# Sheet1.net
KiCad netlist of a schematic drawn in Altium Designer
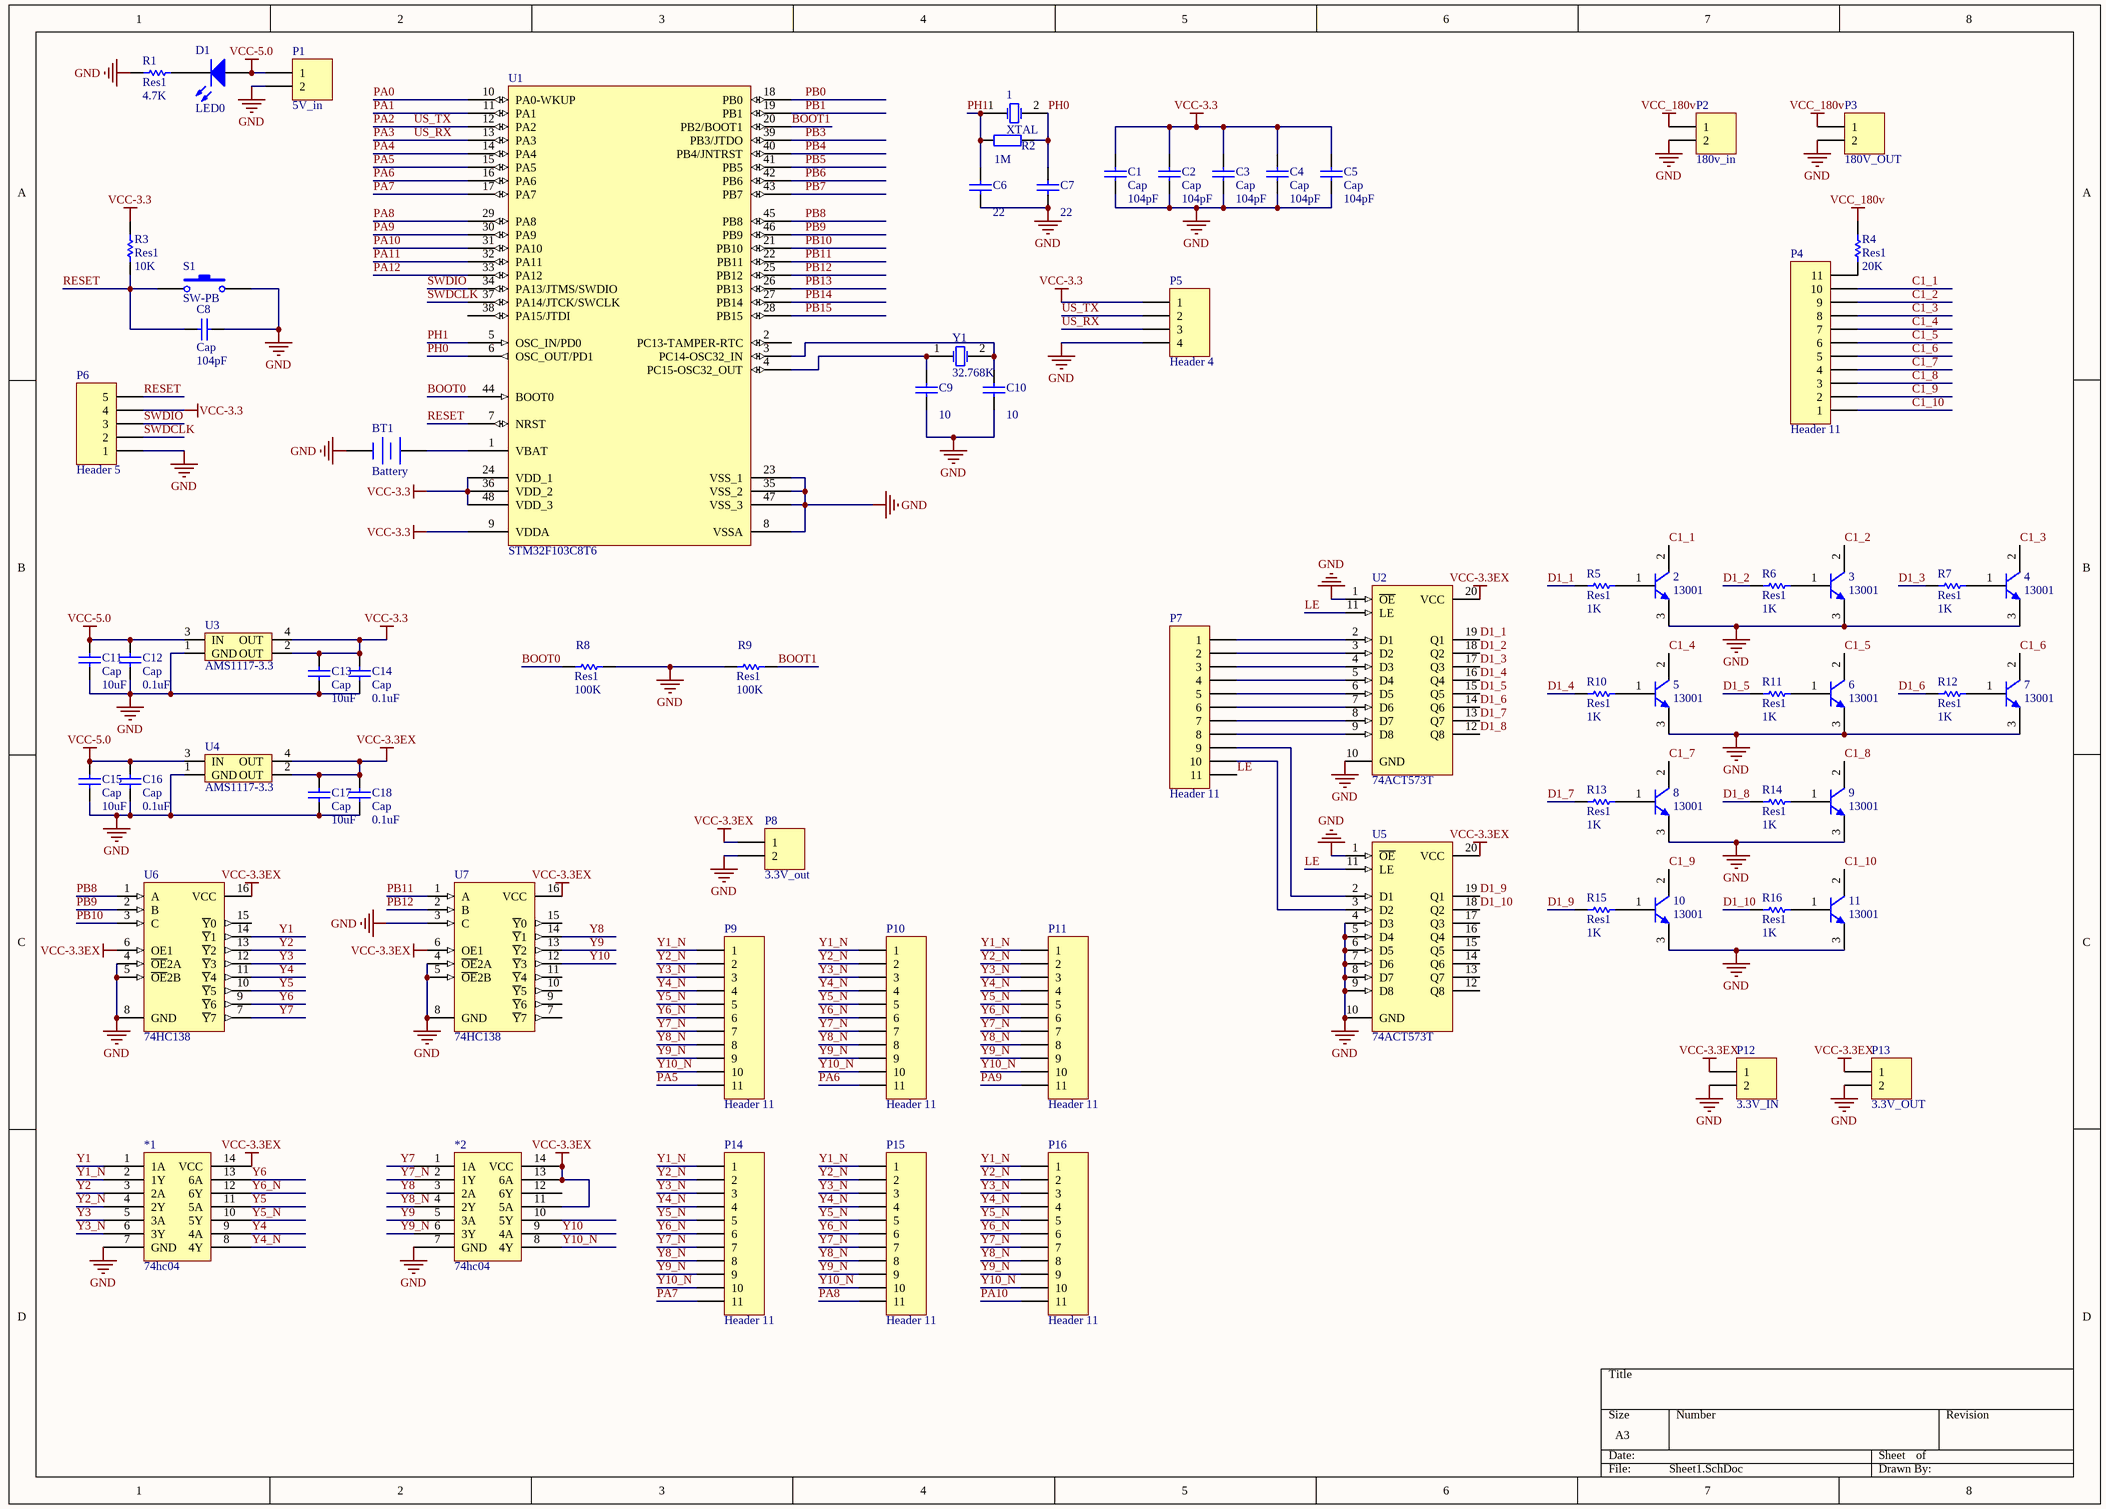
[diagram p0: Sheet1.SchDoc]

(export (version "E")
  (design (tool "Eeschema 10.0.6"))
  (components
    (comp (ref "*1")
      (value "74hc04")
      (footprint "DIP-14")
      (description "非门")
      (libsource (lib "辉光管原理图库") (part "74hc04"))
    )
    (comp (ref "*2")
      (value "74hc04")
      (footprint "DIP-14")
      (description "非门")
      (libsource (lib "辉光管原理图库") (part "74hc04"))
    )
    (comp (ref "1")
      (value "XTAL")
      (footprint "49S-SMD")
      (description "Crystal Oscillator")
      (fields (field (name "PUBLISHER") "Altium Limited"))
      (libsource (lib "Miscellaneous Devices") (part "XTAL"))
    )
    (comp (ref "2")
      (value "13001")
      (footprint "TO-92A")
      (description "NPN三极管")
      (fields (field (name "PUBLISHER") "Altium Limited"))
      (libsource (lib "fszhang(2)") (part "13001"))
    )
    (comp (ref "3")
      (value "13001")
      (footprint "TO-92A")
      (description "NPN三极管")
      (fields (field (name "PUBLISHER") "Altium Limited"))
      (libsource (lib "fszhang(2)") (part "13001"))
    )
    (comp (ref "4")
      (value "13001")
      (footprint "TO-92A")
      (description "NPN三极管")
      (fields (field (name "PUBLISHER") "Altium Limited"))
      (libsource (lib "fszhang(2)") (part "13001"))
    )
    (comp (ref "5")
      (value "13001")
      (footprint "TO-92A")
      (description "NPN三极管")
      (fields (field (name "PUBLISHER") "Altium Limited"))
      (libsource (lib "fszhang(2)") (part "13001"))
    )
    (comp (ref "6")
      (value "13001")
      (footprint "TO-92A")
      (description "NPN三极管")
      (fields (field (name "PUBLISHER") "Altium Limited"))
      (libsource (lib "fszhang(2)") (part "13001"))
    )
    (comp (ref "7")
      (value "13001")
      (footprint "TO-92A")
      (description "NPN三极管")
      (fields (field (name "PUBLISHER") "Altium Limited"))
      (libsource (lib "fszhang(2)") (part "13001"))
    )
    (comp (ref "8")
      (value "13001")
      (footprint "TO-92A")
      (description "NPN三极管")
      (fields (field (name "PUBLISHER") "Altium Limited"))
      (libsource (lib "fszhang(2)") (part "13001"))
    )
    (comp (ref "9")
      (value "13001")
      (footprint "TO-92A")
      (description "NPN三极管")
      (fields (field (name "PUBLISHER") "Altium Limited"))
      (libsource (lib "fszhang(2)") (part "13001"))
    )
    (comp (ref "10")
      (value "13001")
      (footprint "TO-92A")
      (description "NPN三极管")
      (fields (field (name "PUBLISHER") "Altium Limited"))
      (libsource (lib "fszhang(2)") (part "13001"))
    )
    (comp (ref "11")
      (value "13001")
      (footprint "TO-92A")
      (description "NPN三极管")
      (fields (field (name "PUBLISHER") "Altium Limited"))
      (libsource (lib "fszhang(2)") (part "13001"))
    )
    (comp (ref "BT1")
      (value "Battery")
      (footprint "CR1220")
      (description "备份电池")
      (fields (field (name "PUBLISHER") "Altium Limited"))
      (libsource (lib "fszhang(2)") (part "Battery"))
    )
    (comp (ref "C1")
      (value "Cap")
      (footprint "0603-1")
      (description "Capacitor")
      (fields (field (name "ALTIUM_VALUE") "104pF") (field (name "PUBLISHER") "Altium Limited"))
      (libsource (lib "Miscellaneous Devices") (part "Cap"))
    )
    (comp (ref "C2")
      (value "Cap")
      (footprint "0603-1")
      (description "Capacitor")
      (fields (field (name "ALTIUM_VALUE") "104pF") (field (name "PUBLISHER") "Altium Limited"))
      (libsource (lib "Miscellaneous Devices") (part "Cap"))
    )
    (comp (ref "C3")
      (value "Cap")
      (footprint "0603-1")
      (description "Capacitor")
      (fields (field (name "ALTIUM_VALUE") "104pF") (field (name "PUBLISHER") "Altium Limited"))
      (libsource (lib "Miscellaneous Devices") (part "Cap"))
    )
    (comp (ref "C4")
      (value "Cap")
      (footprint "0603-1")
      (description "Capacitor")
      (fields (field (name "ALTIUM_VALUE") "104pF") (field (name "PUBLISHER") "Altium Limited"))
      (libsource (lib "Miscellaneous Devices") (part "Cap"))
    )
    (comp (ref "C5")
      (value "Cap")
      (footprint "0603-1")
      (description "Capacitor")
      (fields (field (name "ALTIUM_VALUE") "104pF") (field (name "PUBLISHER") "Altium Limited"))
      (libsource (lib "Miscellaneous Devices") (part "Cap"))
    )
    (comp (ref "C6")
      (value "22")
      (footprint "0603-1")
      (description "Capacitor")
      (fields (field (name "PUBLISHER") "Altium Limited"))
      (libsource (lib "Miscellaneous Devices") (part "Cap"))
    )
    (comp (ref "C7")
      (value "22")
      (footprint "0603-1")
      (description "Capacitor")
      (fields (field (name "PUBLISHER") "Altium Limited"))
      (libsource (lib "Miscellaneous Devices") (part "Cap"))
    )
    (comp (ref "C8")
      (value "Cap")
      (footprint "0603-1")
      (description "Capacitor")
      (fields (field (name "ALTIUM_VALUE") "104pF") (field (name "PUBLISHER") "Altium Limited"))
      (libsource (lib "Miscellaneous Devices") (part "Cap"))
    )
    (comp (ref "C9")
      (value "10")
      (footprint "0603-1")
      (description "Capacitor")
      (fields (field (name "PUBLISHER") "Altium Limited"))
      (libsource (lib "Miscellaneous Devices") (part "Cap"))
    )
    (comp (ref "C10")
      (value "10")
      (footprint "0603-1")
      (description "Capacitor")
      (fields (field (name "PUBLISHER") "Altium Limited"))
      (libsource (lib "Miscellaneous Devices") (part "Cap"))
    )
    (comp (ref "C11")
      (value "Cap")
      (footprint "0603-1")
      (description "Capacitor")
      (fields (field (name "ALTIUM_VALUE") "10uF") (field (name "PUBLISHER") "Altium Limited"))
      (libsource (lib "Miscellaneous Devices") (part "Cap"))
    )
    (comp (ref "C12")
      (value "Cap")
      (footprint "0603-1")
      (description "Capacitor")
      (fields (field (name "ALTIUM_VALUE") "0.1uF") (field (name "PUBLISHER") "Altium Limited"))
      (libsource (lib "Miscellaneous Devices") (part "Cap"))
    )
    (comp (ref "C13")
      (value "Cap")
      (footprint "0603-1")
      (description "Capacitor")
      (fields (field (name "ALTIUM_VALUE") "10uF") (field (name "PUBLISHER") "Altium Limited"))
      (libsource (lib "Miscellaneous Devices") (part "Cap"))
    )
    (comp (ref "C14")
      (value "Cap")
      (footprint "0603-1")
      (description "Capacitor")
      (fields (field (name "ALTIUM_VALUE") "0.1uF") (field (name "PUBLISHER") "Altium Limited"))
      (libsource (lib "Miscellaneous Devices") (part "Cap"))
    )
    (comp (ref "C15")
      (value "Cap")
      (footprint "0603-1")
      (description "Capacitor")
      (fields (field (name "ALTIUM_VALUE") "10uF") (field (name "PUBLISHER") "Altium Limited"))
      (libsource (lib "Miscellaneous Devices") (part "Cap"))
    )
    (comp (ref "C16")
      (value "Cap")
      (footprint "0603-1")
      (description "Capacitor")
      (fields (field (name "ALTIUM_VALUE") "0.1uF") (field (name "PUBLISHER") "Altium Limited"))
      (libsource (lib "Miscellaneous Devices") (part "Cap"))
    )
    (comp (ref "C17")
      (value "Cap")
      (footprint "0603-1")
      (description "Capacitor")
      (fields (field (name "ALTIUM_VALUE") "10uF") (field (name "PUBLISHER") "Altium Limited"))
      (libsource (lib "Miscellaneous Devices") (part "Cap"))
    )
    (comp (ref "C18")
      (value "Cap")
      (footprint "0603-1")
      (description "Capacitor")
      (fields (field (name "ALTIUM_VALUE") "0.1uF") (field (name "PUBLISHER") "Altium Limited"))
      (libsource (lib "Miscellaneous Devices") (part "Cap"))
    )
    (comp (ref "D1")
      (value "LED0")
      (footprint "LED0805")
      (description "Typical INFRARED GaAs LED")
      (fields (field (name "PUBLISHER") "Altium Limited"))
      (libsource (lib "Miscellaneous Devices") (part "LED0"))
    )
    (comp (ref "P1")
      (value "5V_in")
      (footprint "XH2.54-2")
      (description "Header, 2-Pin")
      (fields (field (name "PUBLISHER") "Altium Limited"))
      (libsource (lib "Miscellaneous Connectors") (part "Header 2"))
    )
    (comp (ref "P2")
      (value "180v_in")
      (footprint "XH2.54-2")
      (description "Header, 2-Pin")
      (fields (field (name "PUBLISHER") "Altium Limited"))
      (libsource (lib "Miscellaneous Connectors") (part "Header 2"))
    )
    (comp (ref "P3")
      (value "180V_OUT")
      (footprint "XH2.54-2")
      (description "Header, 2-Pin")
      (fields (field (name "PUBLISHER") "Altium Limited"))
      (libsource (lib "Miscellaneous Connectors") (part "Header 2"))
    )
    (comp (ref "P4")
      (value "Header 11")
      (footprint "SMT11P")
      (description "Header, 11-Pin")
      (fields (field (name "PUBLISHER") "Altium Limited"))
      (libsource (lib "") (part "Header 11_2"))
    )
    (comp (ref "P5")
      (value "Header 4")
      (footprint "HDR1X4")
      (description "Header, 4-Pin")
      (fields (field (name "PUBLISHER") "Altium Limited"))
      (libsource (lib "Miscellaneous Connectors") (part "Header 4"))
    )
    (comp (ref "P6")
      (value "Header 5")
      (footprint "HDR1X5")
      (description "Header, 5-Pin")
      (fields (field (name "PUBLISHER") "Altium Limited"))
      (libsource (lib "Miscellaneous Connectors") (part "Header 5"))
    )
    (comp (ref "P7")
      (value "Header 11")
      (footprint "SMT11P")
      (description "Header, 11-Pin")
      (fields (field (name "PUBLISHER") "Altium Limited"))
      (libsource (lib "") (part "Header 11_1"))
    )
    (comp (ref "P8")
      (value "3.3V_out")
      (footprint "XH2.54-2")
      (description "Header, 2-Pin")
      (fields (field (name "PUBLISHER") "Altium Limited"))
      (libsource (lib "Miscellaneous Connectors") (part "Header 2"))
    )
    (comp (ref "P9")
      (value "Header 11")
      (footprint "SMT11P")
      (description "Header, 11-Pin")
      (fields (field (name "PUBLISHER") "Altium Limited"))
      (libsource (lib "Miscellaneous Connectors") (part "Header 11"))
    )
    (comp (ref "P10")
      (value "Header 11")
      (footprint "SMT11P")
      (description "Header, 11-Pin")
      (fields (field (name "PUBLISHER") "Altium Limited"))
      (libsource (lib "Miscellaneous Connectors") (part "Header 11"))
    )
    (comp (ref "P11")
      (value "Header 11")
      (footprint "SMT11P")
      (description "Header, 11-Pin")
      (fields (field (name "PUBLISHER") "Altium Limited"))
      (libsource (lib "Miscellaneous Connectors") (part "Header 11"))
    )
    (comp (ref "P12")
      (value "3.3V_IN")
      (footprint "XH2.54-2")
      (description "Header, 2-Pin")
      (fields (field (name "PUBLISHER") "Altium Limited"))
      (libsource (lib "Miscellaneous Connectors") (part "Header 2"))
    )
    (comp (ref "P13")
      (value "3.3V_OUT")
      (footprint "XH2.54-2")
      (description "Header, 2-Pin")
      (fields (field (name "PUBLISHER") "Altium Limited"))
      (libsource (lib "Miscellaneous Connectors") (part "Header 2"))
    )
    (comp (ref "P14")
      (value "Header 11")
      (footprint "SMT11P")
      (description "Header, 11-Pin")
      (fields (field (name "PUBLISHER") "Altium Limited"))
      (libsource (lib "Miscellaneous Connectors") (part "Header 11"))
    )
    (comp (ref "P15")
      (value "Header 11")
      (footprint "SMT11P")
      (description "Header, 11-Pin")
      (fields (field (name "PUBLISHER") "Altium Limited"))
      (libsource (lib "Miscellaneous Connectors") (part "Header 11"))
    )
    (comp (ref "P16")
      (value "Header 11")
      (footprint "SMT11P")
      (description "Header, 11-Pin")
      (fields (field (name "PUBLISHER") "Altium Limited"))
      (libsource (lib "Miscellaneous Connectors") (part "Header 11"))
    )
    (comp (ref "R1")
      (value "Res1")
      (footprint "0603-1")
      (description "Resistor")
      (fields (field (name "ALTIUM_VALUE") "4.7K") (field (name "PUBLISHER") "Altium Limited"))
      (libsource (lib "Miscellaneous Devices") (part "Res1"))
    )
    (comp (ref "R2")
      (value "1M")
      (footprint "0603-1")
      (description "Resistor")
      (fields (field (name "PUBLISHER") "Altium Limited"))
      (libsource (lib "Miscellaneous Devices") (part "Res2"))
    )
    (comp (ref "R3")
      (value "Res1")
      (footprint "0603-1")
      (description "Resistor")
      (fields (field (name "ALTIUM_VALUE") "10K") (field (name "PUBLISHER") "Altium Limited"))
      (libsource (lib "Miscellaneous Devices") (part "Res1"))
    )
    (comp (ref "R4")
      (value "Res1")
      (footprint "0805-1R")
      (description "Resistor")
      (fields (field (name "ALTIUM_VALUE") "20K") (field (name "PUBLISHER") "Altium Limited"))
      (libsource (lib "Miscellaneous Devices") (part "Res1"))
    )
    (comp (ref "R5")
      (value "Res1")
      (footprint "0603R")
      (description "Resistor")
      (fields (field (name "ALTIUM_VALUE") "1K") (field (name "PUBLISHER") "Altium Limited"))
      (libsource (lib "Miscellaneous Devices") (part "Res1"))
    )
    (comp (ref "R6")
      (value "Res1")
      (footprint "0603R")
      (description "Resistor")
      (fields (field (name "ALTIUM_VALUE") "1K") (field (name "PUBLISHER") "Altium Limited"))
      (libsource (lib "Miscellaneous Devices") (part "Res1"))
    )
    (comp (ref "R7")
      (value "Res1")
      (footprint "0603R")
      (description "Resistor")
      (fields (field (name "ALTIUM_VALUE") "1K") (field (name "PUBLISHER") "Altium Limited"))
      (libsource (lib "Miscellaneous Devices") (part "Res1"))
    )
    (comp (ref "R8")
      (value "Res1")
      (footprint "0603-1")
      (description "Resistor")
      (fields (field (name "ALTIUM_VALUE") "100K") (field (name "PUBLISHER") "Altium Limited"))
      (libsource (lib "Miscellaneous Devices") (part "Res1"))
    )
    (comp (ref "R9")
      (value "Res1")
      (footprint "0603-1")
      (description "Resistor")
      (fields (field (name "ALTIUM_VALUE") "100K") (field (name "PUBLISHER") "Altium Limited"))
      (libsource (lib "Miscellaneous Devices") (part "Res1"))
    )
    (comp (ref "R10")
      (value "Res1")
      (footprint "0603R")
      (description "Resistor")
      (fields (field (name "ALTIUM_VALUE") "1K") (field (name "PUBLISHER") "Altium Limited"))
      (libsource (lib "Miscellaneous Devices") (part "Res1"))
    )
    (comp (ref "R11")
      (value "Res1")
      (footprint "0603R")
      (description "Resistor")
      (fields (field (name "ALTIUM_VALUE") "1K") (field (name "PUBLISHER") "Altium Limited"))
      (libsource (lib "Miscellaneous Devices") (part "Res1"))
    )
    (comp (ref "R12")
      (value "Res1")
      (footprint "0603R")
      (description "Resistor")
      (fields (field (name "ALTIUM_VALUE") "1K") (field (name "PUBLISHER") "Altium Limited"))
      (libsource (lib "Miscellaneous Devices") (part "Res1"))
    )
    (comp (ref "R13")
      (value "Res1")
      (footprint "0603R")
      (description "Resistor")
      (fields (field (name "ALTIUM_VALUE") "1K") (field (name "PUBLISHER") "Altium Limited"))
      (libsource (lib "Miscellaneous Devices") (part "Res1"))
    )
    (comp (ref "R14")
      (value "Res1")
      (footprint "0603R")
      (description "Resistor")
      (fields (field (name "ALTIUM_VALUE") "1K") (field (name "PUBLISHER") "Altium Limited"))
      (libsource (lib "Miscellaneous Devices") (part "Res1"))
    )
    (comp (ref "R15")
      (value "Res1")
      (footprint "0603R")
      (description "Resistor")
      (fields (field (name "ALTIUM_VALUE") "1K") (field (name "PUBLISHER") "Altium Limited"))
      (libsource (lib "Miscellaneous Devices") (part "Res1"))
    )
    (comp (ref "R16")
      (value "Res1")
      (footprint "0603R")
      (description "Resistor")
      (fields (field (name "ALTIUM_VALUE") "1K") (field (name "PUBLISHER") "Altium Limited"))
      (libsource (lib "Miscellaneous Devices") (part "Res1"))
    )
    (comp (ref "S1")
      (value "SW-PB")
      (footprint "KEY-SMD1")
      (description "Switch")
      (fields (field (name "PUBLISHER") "Altium Limited"))
      (libsource (lib "Miscellaneous Devices") (part "SW-PB"))
    )
    (comp (ref "U1")
      (value "STM32F103C8T6")
      (footprint "LQFP48_N")
      (description "STM32 ARM-based 32-bit MCU with 64 Kbytes Flash, 48-pin LQFP, Industrial Temperature")
      (fields (field (name "PUBLISHER") "Altium Limited"))
      (libsource (lib "ST Microcontroller 32-Bit STM32") (part "STM32F103C8T6"))
    )
    (comp (ref "U2")
      (value "74ACT573T")
      (footprint "DIP-20")
      (description "双向数据传输")
      (fields (field (name "PUBLISHER") "Altium Limited"))
      (libsource (lib "fszhang(2)") (part "74ACT573T"))
    )
    (comp (ref "U3")
      (value "AMS1117-3.3")
      (footprint "AMS1117")
      (libsource (lib "Explorer STM32F407封装库") (part "AMS1117"))
    )
    (comp (ref "U4")
      (value "AMS1117-3.3")
      (footprint "AMS1117")
      (libsource (lib "Explorer STM32F407封装库") (part "AMS1117"))
    )
    (comp (ref "U5")
      (value "74ACT573T")
      (footprint "DIP-20")
      (description "双向数据传输")
      (fields (field (name "PUBLISHER") "Altium Limited"))
      (libsource (lib "fszhang(2)") (part "74ACT573T"))
    )
    (comp (ref "U6")
      (value "74HC138")
      (footprint "DIP-16")
      (description "138译码器")
      (fields (field (name "PUBLISHER") "Altium Limited"))
      (libsource (lib "fszhang(2)") (part "74HC138"))
    )
    (comp (ref "U7")
      (value "74HC138")
      (footprint "DIP-16")
      (description "138译码器")
      (fields (field (name "PUBLISHER") "Altium Limited"))
      (libsource (lib "fszhang(2)") (part "74HC138"))
    )
    (comp (ref "Y1")
      (value "32.768K")
      (footprint "XTAL32")
      (description "Crystal Oscillator")
      (fields (field (name "PUBLISHER") "Altium Limited"))
      (libsource (lib "Explorer STM32F407封装库") (part "XTAL_1"))
    )
  )
  (nets
    (net (code "1") (name "/BOOT0") (class "Default")
      (node (ref "R8") (pin "1") (pinfunction "1_1") (pintype "passive"))
      (node (ref "U1") (pin "44") (pinfunction "BOOT0_44") (pintype "input"))
    )
    (net (code "2") (name "/BOOT1") (class "Default")
      (node (ref "R9") (pin "2") (pinfunction "2_2") (pintype "passive"))
      (node (ref "U1") (pin "20") (pinfunction "PB2/BOOT1_20") (pintype "bidirectional"))
    )
    (net (code "3") (name "/C1_1") (class "Default")
      (node (ref "2") (pin "2") (pinfunction "C_2") (pintype "passive"))
      (node (ref "P4") (pin "10") (pinfunction "10_10") (pintype "passive"))
    )
    (net (code "4") (name "/C1_2") (class "Default")
      (node (ref "3") (pin "2") (pinfunction "C_2") (pintype "passive"))
      (node (ref "P4") (pin "9") (pinfunction "9_9") (pintype "passive"))
    )
    (net (code "5") (name "/C1_3") (class "Default")
      (node (ref "4") (pin "2") (pinfunction "C_2") (pintype "passive"))
      (node (ref "P4") (pin "8") (pinfunction "8_8") (pintype "passive"))
    )
    (net (code "6") (name "/C1_4") (class "Default")
      (node (ref "5") (pin "2") (pinfunction "C_2") (pintype "passive"))
      (node (ref "P4") (pin "7") (pinfunction "7_7") (pintype "passive"))
    )
    (net (code "7") (name "/C1_5") (class "Default")
      (node (ref "6") (pin "2") (pinfunction "C_2") (pintype "passive"))
      (node (ref "P4") (pin "6") (pinfunction "6_6") (pintype "passive"))
    )
    (net (code "8") (name "/C1_6") (class "Default")
      (node (ref "7") (pin "2") (pinfunction "C_2") (pintype "passive"))
      (node (ref "P4") (pin "5") (pinfunction "5_5") (pintype "passive"))
    )
    (net (code "9") (name "/C1_7") (class "Default")
      (node (ref "8") (pin "2") (pinfunction "C_2") (pintype "passive"))
      (node (ref "P4") (pin "4") (pinfunction "4_4") (pintype "passive"))
    )
    (net (code "10") (name "/C1_8") (class "Default")
      (node (ref "9") (pin "2") (pinfunction "C_2") (pintype "passive"))
      (node (ref "P4") (pin "3") (pinfunction "3_3") (pintype "passive"))
    )
    (net (code "11") (name "/C1_9") (class "Default")
      (node (ref "10") (pin "2") (pinfunction "C_2") (pintype "passive"))
      (node (ref "P4") (pin "2") (pinfunction "2_2") (pintype "passive"))
    )
    (net (code "12") (name "/C1_10") (class "Default")
      (node (ref "11") (pin "2") (pinfunction "C_2") (pintype "passive"))
      (node (ref "P4") (pin "1") (pinfunction "1_1") (pintype "passive"))
    )
    (net (code "13") (name "/D1_1") (class "Default")
      (node (ref "R5") (pin "1") (pinfunction "1_1") (pintype "passive"))
      (node (ref "U2") (pin "19") (pinfunction "Q1_19") (pintype "tri_state"))
    )
    (net (code "14") (name "/D1_2") (class "Default")
      (node (ref "R6") (pin "1") (pinfunction "1_1") (pintype "passive"))
      (node (ref "U2") (pin "18") (pinfunction "Q2_18") (pintype "tri_state"))
    )
    (net (code "15") (name "/D1_3") (class "Default")
      (node (ref "R7") (pin "1") (pinfunction "1_1") (pintype "passive"))
      (node (ref "U2") (pin "17") (pinfunction "Q3_17") (pintype "tri_state"))
    )
    (net (code "16") (name "/D1_4") (class "Default")
      (node (ref "R10") (pin "1") (pinfunction "1_1") (pintype "passive"))
      (node (ref "U2") (pin "16") (pinfunction "Q4_16") (pintype "tri_state"))
    )
    (net (code "17") (name "/D1_5") (class "Default")
      (node (ref "R11") (pin "1") (pinfunction "1_1") (pintype "passive"))
      (node (ref "U2") (pin "15") (pinfunction "Q5_15") (pintype "tri_state"))
    )
    (net (code "18") (name "/D1_6") (class "Default")
      (node (ref "R12") (pin "1") (pinfunction "1_1") (pintype "passive"))
      (node (ref "U2") (pin "14") (pinfunction "Q6_14") (pintype "tri_state"))
    )
    (net (code "19") (name "/D1_7") (class "Default")
      (node (ref "R13") (pin "1") (pinfunction "1_1") (pintype "passive"))
      (node (ref "U2") (pin "13") (pinfunction "Q7_13") (pintype "tri_state"))
    )
    (net (code "20") (name "/D1_8") (class "Default")
      (node (ref "R14") (pin "1") (pinfunction "1_1") (pintype "passive"))
      (node (ref "U2") (pin "12") (pinfunction "Q8_12") (pintype "tri_state"))
    )
    (net (code "21") (name "/D1_9") (class "Default")
      (node (ref "R15") (pin "1") (pinfunction "1_1") (pintype "passive"))
      (node (ref "U5") (pin "19") (pinfunction "Q1_19") (pintype "tri_state"))
    )
    (net (code "22") (name "/D1_10") (class "Default")
      (node (ref "R16") (pin "1") (pinfunction "1_1") (pintype "passive"))
      (node (ref "U5") (pin "18") (pinfunction "Q2_18") (pintype "tri_state"))
    )
    (net (code "23") (name "/LE") (class "Default")
      (node (ref "P7") (pin "11") (pinfunction "11_11") (pintype "passive"))
      (node (ref "U2") (pin "11") (pinfunction "LE_11") (pintype "input"))
      (node (ref "U5") (pin "11") (pinfunction "LE_11") (pintype "input"))
    )
    (net (code "24") (name "/PA0") (class "Default")
      (node (ref "U1") (pin "10") (pinfunction "PA0-WKUP_10") (pintype "bidirectional"))
    )
    (net (code "25") (name "/PA1") (class "Default")
      (node (ref "U1") (pin "11") (pinfunction "PA1_11") (pintype "bidirectional"))
    )
    (net (code "26") (name "/PA2") (class "Default")
      (node (ref "P5") (pin "2") (pinfunction "2_2") (pintype "passive"))
      (node (ref "U1") (pin "12") (pinfunction "PA2_12") (pintype "bidirectional"))
    )
    (net (code "27") (name "/PA3") (class "Default")
      (node (ref "P5") (pin "3") (pinfunction "3_3") (pintype "passive"))
      (node (ref "U1") (pin "13") (pinfunction "PA3_13") (pintype "bidirectional"))
    )
    (net (code "28") (name "/PA4") (class "Default")
      (node (ref "U1") (pin "14") (pinfunction "PA4_14") (pintype "bidirectional"))
    )
    (net (code "29") (name "/PA5") (class "Default")
      (node (ref "P9") (pin "11") (pinfunction "11_11") (pintype "passive"))
      (node (ref "U1") (pin "15") (pinfunction "PA5_15") (pintype "bidirectional"))
    )
    (net (code "30") (name "/PA6") (class "Default")
      (node (ref "P10") (pin "11") (pinfunction "11_11") (pintype "passive"))
      (node (ref "U1") (pin "16") (pinfunction "PA6_16") (pintype "bidirectional"))
    )
    (net (code "31") (name "/PA7") (class "Default")
      (node (ref "P14") (pin "11") (pinfunction "11_11") (pintype "passive"))
      (node (ref "U1") (pin "17") (pinfunction "PA7_17") (pintype "bidirectional"))
    )
    (net (code "32") (name "/PA8") (class "Default")
      (node (ref "P15") (pin "11") (pinfunction "11_11") (pintype "passive"))
      (node (ref "U1") (pin "29") (pinfunction "PA8_29") (pintype "bidirectional"))
    )
    (net (code "33") (name "/PA9") (class "Default")
      (node (ref "P11") (pin "11") (pinfunction "11_11") (pintype "passive"))
      (node (ref "U1") (pin "30") (pinfunction "PA9_30") (pintype "bidirectional"))
    )
    (net (code "34") (name "/PA10") (class "Default")
      (node (ref "P16") (pin "11") (pinfunction "11_11") (pintype "passive"))
      (node (ref "U1") (pin "31") (pinfunction "PA10_31") (pintype "bidirectional"))
    )
    (net (code "35") (name "/PA11") (class "Default")
      (node (ref "U1") (pin "32") (pinfunction "PA11_32") (pintype "bidirectional"))
    )
    (net (code "36") (name "/PA12") (class "Default")
      (node (ref "U1") (pin "33") (pinfunction "PA12_33") (pintype "bidirectional"))
    )
    (net (code "37") (name "/PB0") (class "Default")
      (node (ref "U1") (pin "18") (pinfunction "PB0_18") (pintype "bidirectional"))
    )
    (net (code "38") (name "/PB1") (class "Default")
      (node (ref "U1") (pin "19") (pinfunction "PB1_19") (pintype "bidirectional"))
    )
    (net (code "39") (name "/PB3") (class "Default")
      (node (ref "U1") (pin "39") (pinfunction "PB3/JTDO_39") (pintype "bidirectional"))
    )
    (net (code "40") (name "/PB4") (class "Default")
      (node (ref "U1") (pin "40") (pinfunction "PB4/JNTRST_40") (pintype "bidirectional"))
    )
    (net (code "41") (name "/PB5") (class "Default")
      (node (ref "U1") (pin "41") (pinfunction "PB5_41") (pintype "bidirectional"))
    )
    (net (code "42") (name "/PB6") (class "Default")
      (node (ref "U1") (pin "42") (pinfunction "PB6_42") (pintype "bidirectional"))
    )
    (net (code "43") (name "/PB7") (class "Default")
      (node (ref "U1") (pin "43") (pinfunction "PB7_43") (pintype "bidirectional"))
    )
    (net (code "44") (name "/PB8") (class "Default")
      (node (ref "U1") (pin "45") (pinfunction "PB8_45") (pintype "bidirectional"))
      (node (ref "U6") (pin "1") (pinfunction "A_1") (pintype "input"))
    )
    (net (code "45") (name "/PB9") (class "Default")
      (node (ref "U1") (pin "46") (pinfunction "PB9_46") (pintype "bidirectional"))
      (node (ref "U6") (pin "2") (pinfunction "B_2") (pintype "input"))
    )
    (net (code "46") (name "/PB10") (class "Default")
      (node (ref "U1") (pin "21") (pinfunction "PB10_21") (pintype "bidirectional"))
      (node (ref "U6") (pin "3") (pinfunction "C_3") (pintype "input"))
    )
    (net (code "47") (name "/PB11") (class "Default")
      (node (ref "U1") (pin "22") (pinfunction "PB11_22") (pintype "bidirectional"))
      (node (ref "U7") (pin "1") (pinfunction "A_1") (pintype "input"))
    )
    (net (code "48") (name "/PB12") (class "Default")
      (node (ref "U1") (pin "25") (pinfunction "PB12_25") (pintype "bidirectional"))
      (node (ref "U7") (pin "2") (pinfunction "B_2") (pintype "input"))
    )
    (net (code "49") (name "/PB13") (class "Default")
      (node (ref "U1") (pin "26") (pinfunction "PB13_26") (pintype "bidirectional"))
    )
    (net (code "50") (name "/PB14") (class "Default")
      (node (ref "U1") (pin "27") (pinfunction "PB14_27") (pintype "bidirectional"))
    )
    (net (code "51") (name "/PB15") (class "Default")
      (node (ref "U1") (pin "28") (pinfunction "PB15_28") (pintype "bidirectional"))
    )
    (net (code "52") (name "/PH0") (class "Default")
      (node (ref "1") (pin "2") (pinfunction "OSC2_2") (pintype "passive"))
      (node (ref "C7") (pin "1") (pinfunction "1_1") (pintype "passive"))
      (node (ref "R2") (pin "1") (pinfunction "1_1") (pintype "passive"))
      (node (ref "U1") (pin "6") (pinfunction "OSC_OUT/PD1_6") (pintype "output"))
    )
    (net (code "53") (name "/PH1") (class "Default")
      (node (ref "1") (pin "1") (pinfunction "OSC1_1") (pintype "passive"))
      (node (ref "C6") (pin "2") (pinfunction "2_2") (pintype "passive"))
      (node (ref "R2") (pin "2") (pinfunction "2_2") (pintype "passive"))
      (node (ref "U1") (pin "5") (pinfunction "OSC_IN/PD0_5") (pintype "input"))
    )
    (net (code "54") (name "/RESET") (class "Default")
      (node (ref "C8") (pin "2") (pinfunction "2_2") (pintype "passive"))
      (node (ref "P6") (pin "5") (pinfunction "5_5") (pintype "passive"))
      (node (ref "R3") (pin "1") (pinfunction "1_1") (pintype "passive"))
      (node (ref "S1") (pin "1") (pinfunction "1_1") (pintype "passive"))
      (node (ref "U1") (pin "7") (pinfunction "NRST_7") (pintype "bidirectional"))
    )
    (net (code "55") (name "/SWDCLK") (class "Default")
      (node (ref "P6") (pin "2") (pinfunction "2_2") (pintype "passive"))
      (node (ref "U1") (pin "37") (pinfunction "PA14/JTCK/SWCLK_37") (pintype "bidirectional"))
    )
    (net (code "56") (name "/SWDIO") (class "Default")
      (node (ref "P6") (pin "3") (pinfunction "3_3") (pintype "passive"))
      (node (ref "U1") (pin "34") (pinfunction "PA13/JTMS/SWDIO_34") (pintype "bidirectional"))
    )
    (net (code "57") (name "/Y1") (class "Default")
      (node (ref "*1") (pin "1") (pinfunction "1A_1") (pintype "passive"))
      (node (ref "U6") (pin "14") (pinfunction "~{Y}1_14") (pintype "output"))
    )
    (net (code "58") (name "/Y1_N") (class "Default")
      (node (ref "*1") (pin "2") (pinfunction "1Y_2") (pintype "passive"))
      (node (ref "P10") (pin "1") (pinfunction "1_1") (pintype "passive"))
      (node (ref "P11") (pin "1") (pinfunction "1_1") (pintype "passive"))
      (node (ref "P14") (pin "1") (pinfunction "1_1") (pintype "passive"))
      (node (ref "P15") (pin "1") (pinfunction "1_1") (pintype "passive"))
      (node (ref "P16") (pin "1") (pinfunction "1_1") (pintype "passive"))
      (node (ref "P9") (pin "1") (pinfunction "1_1") (pintype "passive"))
    )
    (net (code "59") (name "/Y2") (class "Default")
      (node (ref "*1") (pin "3") (pinfunction "2A_3") (pintype "passive"))
      (node (ref "U6") (pin "13") (pinfunction "~{Y}2_13") (pintype "output"))
    )
    (net (code "60") (name "/Y2_N") (class "Default")
      (node (ref "*1") (pin "4") (pinfunction "2Y_4") (pintype "passive"))
      (node (ref "P10") (pin "2") (pinfunction "2_2") (pintype "passive"))
      (node (ref "P11") (pin "2") (pinfunction "2_2") (pintype "passive"))
      (node (ref "P14") (pin "2") (pinfunction "2_2") (pintype "passive"))
      (node (ref "P15") (pin "2") (pinfunction "2_2") (pintype "passive"))
      (node (ref "P16") (pin "2") (pinfunction "2_2") (pintype "passive"))
      (node (ref "P9") (pin "2") (pinfunction "2_2") (pintype "passive"))
    )
    (net (code "61") (name "/Y3") (class "Default")
      (node (ref "*1") (pin "5") (pinfunction "3A_5") (pintype "passive"))
      (node (ref "U6") (pin "12") (pinfunction "~{Y}3_12") (pintype "output"))
    )
    (net (code "62") (name "/Y3_N") (class "Default")
      (node (ref "*1") (pin "6") (pinfunction "3Y_6") (pintype "passive"))
      (node (ref "P10") (pin "3") (pinfunction "3_3") (pintype "passive"))
      (node (ref "P11") (pin "3") (pinfunction "3_3") (pintype "passive"))
      (node (ref "P14") (pin "3") (pinfunction "3_3") (pintype "passive"))
      (node (ref "P15") (pin "3") (pinfunction "3_3") (pintype "passive"))
      (node (ref "P16") (pin "3") (pinfunction "3_3") (pintype "passive"))
      (node (ref "P9") (pin "3") (pinfunction "3_3") (pintype "passive"))
    )
    (net (code "63") (name "/Y4") (class "Default")
      (node (ref "*1") (pin "9") (pinfunction "4A_9") (pintype "passive"))
      (node (ref "U6") (pin "11") (pinfunction "~{Y}4_11") (pintype "output"))
    )
    (net (code "64") (name "/Y4_N") (class "Default")
      (node (ref "*1") (pin "8") (pinfunction "4Y_8") (pintype "passive"))
      (node (ref "P10") (pin "4") (pinfunction "4_4") (pintype "passive"))
      (node (ref "P11") (pin "4") (pinfunction "4_4") (pintype "passive"))
      (node (ref "P14") (pin "4") (pinfunction "4_4") (pintype "passive"))
      (node (ref "P15") (pin "4") (pinfunction "4_4") (pintype "passive"))
      (node (ref "P16") (pin "4") (pinfunction "4_4") (pintype "passive"))
      (node (ref "P9") (pin "4") (pinfunction "4_4") (pintype "passive"))
    )
    (net (code "65") (name "/Y5") (class "Default")
      (node (ref "*1") (pin "11") (pinfunction "5A_11") (pintype "passive"))
      (node (ref "U6") (pin "10") (pinfunction "~{Y}5_10") (pintype "output"))
    )
    (net (code "66") (name "/Y5_N") (class "Default")
      (node (ref "*1") (pin "10") (pinfunction "5Y_10") (pintype "passive"))
      (node (ref "P10") (pin "5") (pinfunction "5_5") (pintype "passive"))
      (node (ref "P11") (pin "5") (pinfunction "5_5") (pintype "passive"))
      (node (ref "P14") (pin "5") (pinfunction "5_5") (pintype "passive"))
      (node (ref "P15") (pin "5") (pinfunction "5_5") (pintype "passive"))
      (node (ref "P16") (pin "5") (pinfunction "5_5") (pintype "passive"))
      (node (ref "P9") (pin "5") (pinfunction "5_5") (pintype "passive"))
    )
    (net (code "67") (name "/Y6") (class "Default")
      (node (ref "*1") (pin "13") (pinfunction "6A_13") (pintype "passive"))
      (node (ref "U6") (pin "9") (pinfunction "~{Y}6_9") (pintype "output"))
    )
    (net (code "68") (name "/Y6_N") (class "Default")
      (node (ref "*1") (pin "12") (pinfunction "6Y_12") (pintype "passive"))
      (node (ref "P10") (pin "6") (pinfunction "6_6") (pintype "passive"))
      (node (ref "P11") (pin "6") (pinfunction "6_6") (pintype "passive"))
      (node (ref "P14") (pin "6") (pinfunction "6_6") (pintype "passive"))
      (node (ref "P15") (pin "6") (pinfunction "6_6") (pintype "passive"))
      (node (ref "P16") (pin "6") (pinfunction "6_6") (pintype "passive"))
      (node (ref "P9") (pin "6") (pinfunction "6_6") (pintype "passive"))
    )
    (net (code "69") (name "/Y7") (class "Default")
      (node (ref "*2") (pin "1") (pinfunction "1A_1") (pintype "passive"))
      (node (ref "U6") (pin "7") (pinfunction "~{Y}7_7") (pintype "output"))
    )
    (net (code "70") (name "/Y7_N") (class "Default")
      (node (ref "*2") (pin "2") (pinfunction "1Y_2") (pintype "passive"))
      (node (ref "P10") (pin "7") (pinfunction "7_7") (pintype "passive"))
      (node (ref "P11") (pin "7") (pinfunction "7_7") (pintype "passive"))
      (node (ref "P14") (pin "7") (pinfunction "7_7") (pintype "passive"))
      (node (ref "P15") (pin "7") (pinfunction "7_7") (pintype "passive"))
      (node (ref "P16") (pin "7") (pinfunction "7_7") (pintype "passive"))
      (node (ref "P9") (pin "7") (pinfunction "7_7") (pintype "passive"))
    )
    (net (code "71") (name "/Y8") (class "Default")
      (node (ref "*2") (pin "3") (pinfunction "2A_3") (pintype "passive"))
      (node (ref "U7") (pin "14") (pinfunction "~{Y}1_14") (pintype "output"))
    )
    (net (code "72") (name "/Y8_N") (class "Default")
      (node (ref "*2") (pin "4") (pinfunction "2Y_4") (pintype "passive"))
      (node (ref "P10") (pin "8") (pinfunction "8_8") (pintype "passive"))
      (node (ref "P11") (pin "8") (pinfunction "8_8") (pintype "passive"))
      (node (ref "P14") (pin "8") (pinfunction "8_8") (pintype "passive"))
      (node (ref "P15") (pin "8") (pinfunction "8_8") (pintype "passive"))
      (node (ref "P16") (pin "8") (pinfunction "8_8") (pintype "passive"))
      (node (ref "P9") (pin "8") (pinfunction "8_8") (pintype "passive"))
    )
    (net (code "73") (name "/Y9") (class "Default")
      (node (ref "*2") (pin "5") (pinfunction "3A_5") (pintype "passive"))
      (node (ref "U7") (pin "13") (pinfunction "~{Y}2_13") (pintype "output"))
    )
    (net (code "74") (name "/Y9_N") (class "Default")
      (node (ref "*2") (pin "6") (pinfunction "3Y_6") (pintype "passive"))
      (node (ref "P10") (pin "9") (pinfunction "9_9") (pintype "passive"))
      (node (ref "P11") (pin "9") (pinfunction "9_9") (pintype "passive"))
      (node (ref "P14") (pin "9") (pinfunction "9_9") (pintype "passive"))
      (node (ref "P15") (pin "9") (pinfunction "9_9") (pintype "passive"))
      (node (ref "P16") (pin "9") (pinfunction "9_9") (pintype "passive"))
      (node (ref "P9") (pin "9") (pinfunction "9_9") (pintype "passive"))
    )
    (net (code "75") (name "/Y10") (class "Default")
      (node (ref "*2") (pin "9") (pinfunction "4A_9") (pintype "passive"))
      (node (ref "U7") (pin "12") (pinfunction "~{Y}3_12") (pintype "output"))
    )
    (net (code "76") (name "/Y10_N") (class "Default")
      (node (ref "*2") (pin "8") (pinfunction "4Y_8") (pintype "passive"))
      (node (ref "P10") (pin "10") (pinfunction "10_10") (pintype "passive"))
      (node (ref "P11") (pin "10") (pinfunction "10_10") (pintype "passive"))
      (node (ref "P14") (pin "10") (pinfunction "10_10") (pintype "passive"))
      (node (ref "P15") (pin "10") (pinfunction "10_10") (pintype "passive"))
      (node (ref "P16") (pin "10") (pinfunction "10_10") (pintype "passive"))
      (node (ref "P9") (pin "10") (pinfunction "10_10") (pintype "passive"))
    )
    (net (code "77") (name "GND") (class "Default")
      (node (ref "*1") (pin "7") (pinfunction "GND_7") (pintype "passive"))
      (node (ref "*2") (pin "7") (pinfunction "GND_7") (pintype "passive"))
      (node (ref "10") (pin "3") (pinfunction "E_3") (pintype "passive"))
      (node (ref "11") (pin "3") (pinfunction "E_3") (pintype "passive"))
      (node (ref "2") (pin "3") (pinfunction "E_3") (pintype "passive"))
      (node (ref "3") (pin "3") (pinfunction "E_3") (pintype "passive"))
      (node (ref "4") (pin "3") (pinfunction "E_3") (pintype "passive"))
      (node (ref "5") (pin "3") (pinfunction "E_3") (pintype "passive"))
      (node (ref "6") (pin "3") (pinfunction "E_3") (pintype "passive"))
      (node (ref "7") (pin "3") (pinfunction "E_3") (pintype "passive"))
      (node (ref "8") (pin "3") (pinfunction "E_3") (pintype "passive"))
      (node (ref "9") (pin "3") (pinfunction "E_3") (pintype "passive"))
      (node (ref "BT1") (pin "2") (pinfunction "-_2") (pintype "passive"))
      (node (ref "C1") (pin "2") (pinfunction "2_2") (pintype "passive"))
      (node (ref "C10") (pin "2") (pinfunction "2_2") (pintype "passive"))
      (node (ref "C11") (pin "1") (pinfunction "1_1") (pintype "passive"))
      (node (ref "C12") (pin "1") (pinfunction "1_1") (pintype "passive"))
      (node (ref "C13") (pin "1") (pinfunction "1_1") (pintype "passive"))
      (node (ref "C14") (pin "1") (pinfunction "1_1") (pintype "passive"))
      (node (ref "C15") (pin "1") (pinfunction "1_1") (pintype "passive"))
      (node (ref "C16") (pin "1") (pinfunction "1_1") (pintype "passive"))
      (node (ref "C17") (pin "1") (pinfunction "1_1") (pintype "passive"))
      (node (ref "C18") (pin "1") (pinfunction "1_1") (pintype "passive"))
      (node (ref "C2") (pin "2") (pinfunction "2_2") (pintype "passive"))
      (node (ref "C3") (pin "2") (pinfunction "2_2") (pintype "passive"))
      (node (ref "C4") (pin "2") (pinfunction "2_2") (pintype "passive"))
      (node (ref "C5") (pin "2") (pinfunction "2_2") (pintype "passive"))
      (node (ref "C6") (pin "1") (pinfunction "1_1") (pintype "passive"))
      (node (ref "C7") (pin "2") (pinfunction "2_2") (pintype "passive"))
      (node (ref "C8") (pin "1") (pinfunction "1_1") (pintype "passive"))
      (node (ref "C9") (pin "1") (pinfunction "1_1") (pintype "passive"))
      (node (ref "P1") (pin "2") (pinfunction "2_2") (pintype "passive"))
      (node (ref "P12") (pin "2") (pinfunction "2_2") (pintype "passive"))
      (node (ref "P13") (pin "2") (pinfunction "2_2") (pintype "passive"))
      (node (ref "P2") (pin "2") (pinfunction "2_2") (pintype "passive"))
      (node (ref "P3") (pin "2") (pinfunction "2_2") (pintype "passive"))
      (node (ref "P5") (pin "4") (pinfunction "4_4") (pintype "passive"))
      (node (ref "P6") (pin "1") (pinfunction "1_1") (pintype "passive"))
      (node (ref "P8") (pin "2") (pinfunction "2_2") (pintype "passive"))
      (node (ref "R1") (pin "1") (pinfunction "1_1") (pintype "passive"))
      (node (ref "R8") (pin "2") (pinfunction "2_2") (pintype "passive"))
      (node (ref "R9") (pin "1") (pinfunction "1_1") (pintype "passive"))
      (node (ref "S1") (pin "2") (pinfunction "2_2") (pintype "passive"))
      (node (ref "U1") (pin "23") (pinfunction "VSS_1_23") (pintype "power_in"))
      (node (ref "U1") (pin "35") (pinfunction "VSS_2_35") (pintype "power_in"))
      (node (ref "U1") (pin "47") (pinfunction "VSS_3_47") (pintype "power_in"))
      (node (ref "U1") (pin "8") (pinfunction "VSSA_8") (pintype "power_in"))
      (node (ref "U2") (pin "1") (pinfunction "~{OE}_1") (pintype "input"))
      (node (ref "U2") (pin "10") (pinfunction "GND_10") (pintype "power_in"))
      (node (ref "U3") (pin "1") (pinfunction "GND_1") (pintype "passive"))
      (node (ref "U4") (pin "1") (pinfunction "GND_1") (pintype "passive"))
      (node (ref "U5") (pin "1") (pinfunction "~{OE}_1") (pintype "input"))
      (node (ref "U5") (pin "10") (pinfunction "GND_10") (pintype "power_in"))
      (node (ref "U5") (pin "4") (pinfunction "D3_4") (pintype "input"))
      (node (ref "U5") (pin "5") (pinfunction "D4_5") (pintype "input"))
      (node (ref "U5") (pin "6") (pinfunction "D5_6") (pintype "input"))
      (node (ref "U5") (pin "7") (pinfunction "D6_7") (pintype "input"))
      (node (ref "U5") (pin "8") (pinfunction "D7_8") (pintype "input"))
      (node (ref "U5") (pin "9") (pinfunction "D8_9") (pintype "input"))
      (node (ref "U6") (pin "4") (pinfunction "~{OE}2A_4") (pintype "input"))
      (node (ref "U6") (pin "5") (pinfunction "~{OE}2B_5") (pintype "input"))
      (node (ref "U6") (pin "8") (pinfunction "GND_8") (pintype "power_in"))
      (node (ref "U7") (pin "3") (pinfunction "C_3") (pintype "input"))
      (node (ref "U7") (pin "4") (pinfunction "~{OE}2A_4") (pintype "input"))
      (node (ref "U7") (pin "5") (pinfunction "~{OE}2B_5") (pintype "input"))
      (node (ref "U7") (pin "8") (pinfunction "GND_8") (pintype "power_in"))
    )
    (net (code "78") (name "Net-(2-B)") (class "Default")
      (node (ref "2") (pin "1") (pinfunction "B_1") (pintype "passive"))
      (node (ref "R5") (pin "2") (pinfunction "2_2") (pintype "passive"))
    )
    (net (code "79") (name "Net-(3-B)") (class "Default")
      (node (ref "3") (pin "1") (pinfunction "B_1") (pintype "passive"))
      (node (ref "R6") (pin "2") (pinfunction "2_2") (pintype "passive"))
    )
    (net (code "80") (name "Net-(4-B)") (class "Default")
      (node (ref "4") (pin "1") (pinfunction "B_1") (pintype "passive"))
      (node (ref "R7") (pin "2") (pinfunction "2_2") (pintype "passive"))
    )
    (net (code "81") (name "Net-(5-B)") (class "Default")
      (node (ref "5") (pin "1") (pinfunction "B_1") (pintype "passive"))
      (node (ref "R10") (pin "2") (pinfunction "2_2") (pintype "passive"))
    )
    (net (code "82") (name "Net-(6-B)") (class "Default")
      (node (ref "6") (pin "1") (pinfunction "B_1") (pintype "passive"))
      (node (ref "R11") (pin "2") (pinfunction "2_2") (pintype "passive"))
    )
    (net (code "83") (name "Net-(7-B)") (class "Default")
      (node (ref "7") (pin "1") (pinfunction "B_1") (pintype "passive"))
      (node (ref "R12") (pin "2") (pinfunction "2_2") (pintype "passive"))
    )
    (net (code "84") (name "Net-(8-B)") (class "Default")
      (node (ref "8") (pin "1") (pinfunction "B_1") (pintype "passive"))
      (node (ref "R13") (pin "2") (pinfunction "2_2") (pintype "passive"))
    )
    (net (code "85") (name "Net-(9-B)") (class "Default")
      (node (ref "9") (pin "1") (pinfunction "B_1") (pintype "passive"))
      (node (ref "R14") (pin "2") (pinfunction "2_2") (pintype "passive"))
    )
    (net (code "86") (name "Net-(10-B)") (class "Default")
      (node (ref "10") (pin "1") (pinfunction "B_1") (pintype "passive"))
      (node (ref "R15") (pin "2") (pinfunction "2_2") (pintype "passive"))
    )
    (net (code "87") (name "Net-(11-B)") (class "Default")
      (node (ref "11") (pin "1") (pinfunction "B_1") (pintype "passive"))
      (node (ref "R16") (pin "2") (pinfunction "2_2") (pintype "passive"))
    )
    (net (code "88") (name "Net-(BT1-+)") (class "Default")
      (node (ref "BT1") (pin "1") (pinfunction "+_1") (pintype "passive"))
      (node (ref "U1") (pin "1") (pinfunction "VBAT_1") (pintype "power_in"))
    )
    (net (code "89") (name "Net-(D1-K)") (class "Default")
      (node (ref "D1") (pin "2") (pinfunction "K_2") (pintype "passive"))
      (node (ref "R1") (pin "2") (pinfunction "2_2") (pintype "passive"))
    )
    (net (code "90") (name "Net-(P4-Pad11)") (class "Default")
      (node (ref "P4") (pin "11") (pinfunction "11_11") (pintype "passive"))
      (node (ref "R4") (pin "1") (pinfunction "1_1") (pintype "passive"))
    )
    (net (code "91") (name "Net-(U1-PC14-OSC32_IN)") (class "Default")
      (node (ref "C10") (pin "1") (pinfunction "1_1") (pintype "passive"))
      (node (ref "U1") (pin "3") (pinfunction "PC14-OSC32_IN_3") (pintype "bidirectional"))
      (node (ref "Y1") (pin "2") (pinfunction "OSC2_2") (pintype "passive"))
    )
    (net (code "92") (name "Net-(U1-PC15-OSC32_OUT)") (class "Default")
      (node (ref "C9") (pin "2") (pinfunction "2_2") (pintype "passive"))
      (node (ref "U1") (pin "4") (pinfunction "PC15-OSC32_OUT_4") (pintype "bidirectional"))
      (node (ref "Y1") (pin "1") (pinfunction "OSC1_1") (pintype "passive"))
    )
    (net (code "93") (name "Net-(U2-D1)") (class "Default")
      (node (ref "P7") (pin "1") (pinfunction "1_1") (pintype "passive"))
      (node (ref "U2") (pin "2") (pinfunction "D1_2") (pintype "input"))
    )
    (net (code "94") (name "Net-(U2-D2)") (class "Default")
      (node (ref "P7") (pin "2") (pinfunction "2_2") (pintype "passive"))
      (node (ref "U2") (pin "3") (pinfunction "D2_3") (pintype "input"))
    )
    (net (code "95") (name "Net-(U2-D3)") (class "Default")
      (node (ref "P7") (pin "3") (pinfunction "3_3") (pintype "passive"))
      (node (ref "U2") (pin "4") (pinfunction "D3_4") (pintype "input"))
    )
    (net (code "96") (name "Net-(U2-D4)") (class "Default")
      (node (ref "P7") (pin "4") (pinfunction "4_4") (pintype "passive"))
      (node (ref "U2") (pin "5") (pinfunction "D4_5") (pintype "input"))
    )
    (net (code "97") (name "Net-(U2-D5)") (class "Default")
      (node (ref "P7") (pin "5") (pinfunction "5_5") (pintype "passive"))
      (node (ref "U2") (pin "6") (pinfunction "D5_6") (pintype "input"))
    )
    (net (code "98") (name "Net-(U2-D6)") (class "Default")
      (node (ref "P7") (pin "6") (pinfunction "6_6") (pintype "passive"))
      (node (ref "U2") (pin "7") (pinfunction "D6_7") (pintype "input"))
    )
    (net (code "99") (name "Net-(U2-D7)") (class "Default")
      (node (ref "P7") (pin "7") (pinfunction "7_7") (pintype "passive"))
      (node (ref "U2") (pin "8") (pinfunction "D7_8") (pintype "input"))
    )
    (net (code "100") (name "Net-(U2-D8)") (class "Default")
      (node (ref "P7") (pin "8") (pinfunction "8_8") (pintype "passive"))
      (node (ref "U2") (pin "9") (pinfunction "D8_9") (pintype "input"))
    )
    (net (code "101") (name "Net-(U5-D1)") (class "Default")
      (node (ref "P7") (pin "9") (pinfunction "9_9") (pintype "passive"))
      (node (ref "U5") (pin "2") (pinfunction "D1_2") (pintype "input"))
    )
    (net (code "102") (name "Net-(U5-D2)") (class "Default")
      (node (ref "P7") (pin "10") (pinfunction "10_10") (pintype "passive"))
      (node (ref "U5") (pin "3") (pinfunction "D2_3") (pintype "input"))
    )
    (net (code "103") (name "VCC-3.3") (class "Default")
      (node (ref "C1") (pin "1") (pinfunction "1_1") (pintype "passive"))
      (node (ref "C13") (pin "2") (pinfunction "2_2") (pintype "passive"))
      (node (ref "C14") (pin "2") (pinfunction "2_2") (pintype "passive"))
      (node (ref "C2") (pin "1") (pinfunction "1_1") (pintype "passive"))
      (node (ref "C3") (pin "1") (pinfunction "1_1") (pintype "passive"))
      (node (ref "C4") (pin "1") (pinfunction "1_1") (pintype "passive"))
      (node (ref "C5") (pin "1") (pinfunction "1_1") (pintype "passive"))
      (node (ref "P5") (pin "1") (pinfunction "1_1") (pintype "passive"))
      (node (ref "P6") (pin "4") (pinfunction "4_4") (pintype "passive"))
      (node (ref "R3") (pin "2") (pinfunction "2_2") (pintype "passive"))
      (node (ref "U1") (pin "24") (pinfunction "VDD_1_24") (pintype "power_in"))
      (node (ref "U1") (pin "36") (pinfunction "VDD_2_36") (pintype "power_in"))
      (node (ref "U1") (pin "48") (pinfunction "VDD_3_48") (pintype "power_in"))
      (node (ref "U1") (pin "9") (pinfunction "VDDA_9") (pintype "power_in"))
      (node (ref "U3") (pin "2") (pinfunction "OUT_2") (pintype "passive"))
      (node (ref "U3") (pin "4") (pinfunction "OUT_4") (pintype "passive"))
    )
    (net (code "104") (name "VCC-3.3EX") (class "Default")
      (node (ref "*1") (pin "14") (pinfunction "VCC_14") (pintype "passive"))
      (node (ref "*2") (pin "11") (pinfunction "5A_11") (pintype "passive"))
      (node (ref "*2") (pin "13") (pinfunction "6A_13") (pintype "passive"))
      (node (ref "*2") (pin "14") (pinfunction "VCC_14") (pintype "passive"))
      (node (ref "C17") (pin "2") (pinfunction "2_2") (pintype "passive"))
      (node (ref "C18") (pin "2") (pinfunction "2_2") (pintype "passive"))
      (node (ref "P12") (pin "1") (pinfunction "1_1") (pintype "passive"))
      (node (ref "P13") (pin "1") (pinfunction "1_1") (pintype "passive"))
      (node (ref "P8") (pin "1") (pinfunction "1_1") (pintype "passive"))
      (node (ref "U2") (pin "20") (pinfunction "VCC_20") (pintype "power_in"))
      (node (ref "U4") (pin "2") (pinfunction "OUT_2") (pintype "passive"))
      (node (ref "U4") (pin "4") (pinfunction "OUT_4") (pintype "passive"))
      (node (ref "U5") (pin "20") (pinfunction "VCC_20") (pintype "power_in"))
      (node (ref "U6") (pin "16") (pinfunction "VCC_16") (pintype "power_in"))
      (node (ref "U6") (pin "6") (pinfunction "OE1_6") (pintype "input"))
      (node (ref "U7") (pin "16") (pinfunction "VCC_16") (pintype "power_in"))
      (node (ref "U7") (pin "6") (pinfunction "OE1_6") (pintype "input"))
    )
    (net (code "105") (name "VCC-5.0") (class "Default")
      (node (ref "C11") (pin "2") (pinfunction "2_2") (pintype "passive"))
      (node (ref "C12") (pin "2") (pinfunction "2_2") (pintype "passive"))
      (node (ref "C15") (pin "2") (pinfunction "2_2") (pintype "passive"))
      (node (ref "C16") (pin "2") (pinfunction "2_2") (pintype "passive"))
      (node (ref "D1") (pin "1") (pinfunction "A_1") (pintype "passive"))
      (node (ref "P1") (pin "1") (pinfunction "1_1") (pintype "passive"))
      (node (ref "U3") (pin "3") (pinfunction "IN_3") (pintype "passive"))
      (node (ref "U4") (pin "3") (pinfunction "IN_3") (pintype "passive"))
    )
    (net (code "106") (name "VCC_180v") (class "Default")
      (node (ref "P2") (pin "1") (pinfunction "1_1") (pintype "passive"))
      (node (ref "P3") (pin "1") (pinfunction "1_1") (pintype "passive"))
      (node (ref "R4") (pin "2") (pinfunction "2_2") (pintype "passive"))
    )
    (net (code "107") (name "unconnected-(*2-5Y-Pad10)") (class "Default")
      (node (ref "*2") (pin "10") (pinfunction "5Y_10") (pintype "passive"))
    )
    (net (code "108") (name "unconnected-(*2-6Y-Pad12)") (class "Default")
      (node (ref "*2") (pin "12") (pinfunction "6Y_12") (pintype "passive"))
    )
    (net (code "109") (name "unconnected-(U1-PA15{slash}JTDI-Pad38)") (class "Default")
      (node (ref "U1") (pin "38") (pinfunction "PA15/JTDI_38") (pintype "bidirectional"))
    )
    (net (code "110") (name "unconnected-(U1-PC13-TAMPER-RTC-Pad2)") (class "Default")
      (node (ref "U1") (pin "2") (pinfunction "PC13-TAMPER-RTC_2") (pintype "bidirectional"))
    )
    (net (code "111") (name "unconnected-(U5-Q3-Pad17)") (class "Default")
      (node (ref "U5") (pin "17") (pinfunction "Q3_17") (pintype "tri_state"))
    )
    (net (code "112") (name "unconnected-(U5-Q4-Pad16)") (class "Default")
      (node (ref "U5") (pin "16") (pinfunction "Q4_16") (pintype "tri_state"))
    )
    (net (code "113") (name "unconnected-(U5-Q5-Pad15)") (class "Default")
      (node (ref "U5") (pin "15") (pinfunction "Q5_15") (pintype "tri_state"))
    )
    (net (code "114") (name "unconnected-(U5-Q6-Pad14)") (class "Default")
      (node (ref "U5") (pin "14") (pinfunction "Q6_14") (pintype "tri_state"))
    )
    (net (code "115") (name "unconnected-(U5-Q7-Pad13)") (class "Default")
      (node (ref "U5") (pin "13") (pinfunction "Q7_13") (pintype "tri_state"))
    )
    (net (code "116") (name "unconnected-(U5-Q8-Pad12)") (class "Default")
      (node (ref "U5") (pin "12") (pinfunction "Q8_12") (pintype "tri_state"))
    )
    (net (code "117") (name "unconnected-(U6-~{Y}0-Pad15)") (class "Default")
      (node (ref "U6") (pin "15") (pinfunction "~{Y}0_15") (pintype "output"))
    )
    (net (code "118") (name "unconnected-(U7-~{Y}0-Pad15)") (class "Default")
      (node (ref "U7") (pin "15") (pinfunction "~{Y}0_15") (pintype "output"))
    )
    (net (code "119") (name "unconnected-(U7-~{Y}4-Pad11)") (class "Default")
      (node (ref "U7") (pin "11") (pinfunction "~{Y}4_11") (pintype "output"))
    )
    (net (code "120") (name "unconnected-(U7-~{Y}5-Pad10)") (class "Default")
      (node (ref "U7") (pin "10") (pinfunction "~{Y}5_10") (pintype "output"))
    )
    (net (code "121") (name "unconnected-(U7-~{Y}6-Pad9)") (class "Default")
      (node (ref "U7") (pin "9") (pinfunction "~{Y}6_9") (pintype "output"))
    )
    (net (code "122") (name "unconnected-(U7-~{Y}7-Pad7)") (class "Default")
      (node (ref "U7") (pin "7") (pinfunction "~{Y}7_7") (pintype "output"))
    )
  )
)
